# full-bridge-driver.net
KiCad netlist of a schematic drawn in Altium Designer
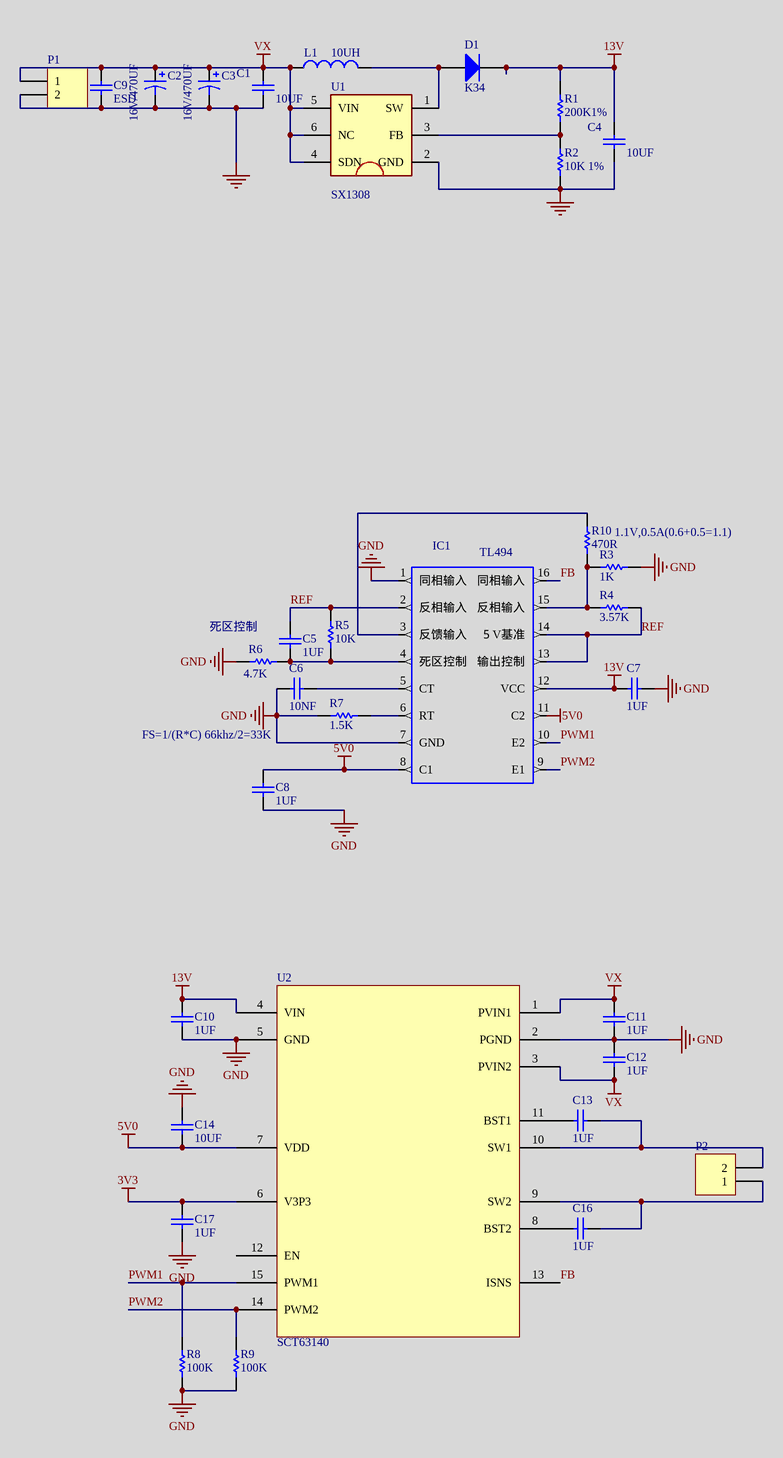
[diagram p0: full-bridge-driver.SchDoc]

(export (version "E")
  (design (tool "Eeschema 10.0.6"))
  (components
    (comp (ref "C1")
      (value "10UF")
      (footprint "C1608-0603N")
      (description "Capacitor")
      (fields
        (field (name "MANUFACTURER") "Generic Components")
        (field (name "PUBLISHER") "Altium Hobart Technology Centre")
      )
      (libsource (lib "Miscellaneous Devices") (part "Cap"))
    )
    (comp (ref "C2")
      (value "16V/470UF")
      (footprint "EC_8mm - 3.5MM")
      (description "Polarized Capacitor (Surface Mount)")
      (fields (field (name "PUBLISHER") "Altium Limited"))
      (libsource (lib "Miscellaneous Devices") (part "Cap Pol3"))
    )
    (comp (ref "C3")
      (value "16V/470UF")
      (footprint "EC_8mm - 3.5MM")
      (description "Polarized Capacitor (Surface Mount)")
      (fields (field (name "PUBLISHER") "Altium Limited"))
      (libsource (lib "Miscellaneous Devices") (part "Cap Pol3"))
    )
    (comp (ref "C4")
      (value "10UF")
      (footprint "C1608-0603N")
      (description "Capacitor")
      (fields
        (field (name "MANUFACTURER") "Generic Components")
        (field (name "PUBLISHER") "Altium Hobart Technology Centre")
      )
      (libsource (lib "Miscellaneous Devices") (part "Cap"))
    )
    (comp (ref "C5")
      (value "1UF")
      (footprint "C1608-0603N")
      (description "Capacitor")
      (fields
        (field (name "MANUFACTURER") "Generic Components")
        (field (name "PUBLISHER") "Altium Hobart Technology Centre")
      )
      (libsource (lib "Miscellaneous Devices") (part "Cap"))
    )
    (comp (ref "C6")
      (value "10NF")
      (footprint "C1608-0603N")
      (description "Capacitor")
      (fields
        (field (name "MANUFACTURER") "Generic Components")
        (field (name "PUBLISHER") "Altium Hobart Technology Centre")
      )
      (libsource (lib "Miscellaneous Devices") (part "Cap"))
    )
    (comp (ref "C7")
      (value "1UF")
      (footprint "C1608-0603N")
      (description "Capacitor")
      (fields
        (field (name "MANUFACTURER") "Generic Components")
        (field (name "PUBLISHER") "Altium Hobart Technology Centre")
      )
      (libsource (lib "Miscellaneous Devices") (part "Cap"))
    )
    (comp (ref "C8")
      (value "1UF")
      (footprint "C1608-0603N")
      (description "Capacitor")
      (fields
        (field (name "MANUFACTURER") "Generic Components")
        (field (name "PUBLISHER") "Altium Hobart Technology Centre")
      )
      (libsource (lib "Miscellaneous Devices") (part "Cap"))
    )
    (comp (ref "C9")
      (value "ESD")
      (footprint "C1608-0603N")
      (description "压敏电阻")
      (libsource (lib "WSK_Lib") (part "Cap"))
    )
    (comp (ref "C10")
      (value "1UF")
      (footprint "C1608-0603N")
      (description "Capacitor")
      (fields
        (field (name "MANUFACTURER") "Generic Components")
        (field (name "PUBLISHER") "Altium Hobart Technology Centre")
      )
      (libsource (lib "Miscellaneous Devices") (part "Cap"))
    )
    (comp (ref "C11")
      (value "1UF")
      (footprint "C1608-0603N")
      (description "Capacitor")
      (fields
        (field (name "MANUFACTURER") "Generic Components")
        (field (name "PUBLISHER") "Altium Hobart Technology Centre")
      )
      (libsource (lib "Miscellaneous Devices") (part "Cap"))
    )
    (comp (ref "C12")
      (value "1UF")
      (footprint "C1608-0603N")
      (description "Capacitor")
      (fields
        (field (name "MANUFACTURER") "Generic Components")
        (field (name "PUBLISHER") "Altium Hobart Technology Centre")
      )
      (libsource (lib "Miscellaneous Devices") (part "Cap"))
    )
    (comp (ref "C13")
      (value "1UF")
      (footprint "C1608-0603N")
      (description "Capacitor")
      (fields
        (field (name "MANUFACTURER") "Generic Components")
        (field (name "PUBLISHER") "Altium Hobart Technology Centre")
      )
      (libsource (lib "Miscellaneous Devices") (part "Cap"))
    )
    (comp (ref "C14")
      (value "10UF")
      (footprint "C1608-0603N")
      (description "Capacitor")
      (fields
        (field (name "MANUFACTURER") "Generic Components")
        (field (name "PUBLISHER") "Altium Hobart Technology Centre")
      )
      (libsource (lib "Miscellaneous Devices") (part "Cap"))
    )
    (comp (ref "C16")
      (value "1UF")
      (footprint "C1608-0603N")
      (description "Capacitor")
      (fields
        (field (name "MANUFACTURER") "Generic Components")
        (field (name "PUBLISHER") "Altium Hobart Technology Centre")
      )
      (libsource (lib "Miscellaneous Devices") (part "Cap"))
    )
    (comp (ref "C17")
      (value "1UF")
      (footprint "C1608-0603N")
      (description "Capacitor")
      (fields
        (field (name "MANUFACTURER") "Generic Components")
        (field (name "PUBLISHER") "Altium Hobart Technology Centre")
      )
      (libsource (lib "Miscellaneous Devices") (part "Cap"))
    )
    (comp (ref "D1")
      (value "K34")
      (footprint "DIODE_1206N")
      (description "Default Diode")
      (fields
        (field (name "MANUFACTURER") "Generic Components")
        (field (name "PUBLISHER") "Altium Hobart Technology Centre")
      )
      (libsource (lib "Miscellaneous Devices") (part "Diode"))
    )
    (comp (ref "IC1") (value "TL494") (footprint "SOP16") (libsource (lib "*") (part "TL494")))
    (comp (ref "L1")
      (value "10UH")
      (footprint "252010")
      (description "Inductor")
      (fields (field (name "PUBLISHER") "Altium Limited"))
      (libsource (lib "Miscellaneous Devices") (part "Inductor"))
    )
    (comp (ref "P1")
      (value "~")
      (footprint "XHB_2pin_2.54mm")
      (description "Header, 2-Pin")
      (fields (field (name "PUBLISHER") "Altium Limited"))
      (libsource (lib "Miscellaneous Connectors") (part "Header 2"))
    )
    (comp (ref "P2")
      (value "~")
      (footprint "XHB_2pin_2.54mm")
      (description "Header, 2-Pin")
      (fields (field (name "PUBLISHER") "Altium Limited"))
      (libsource (lib "") (part "Header 2_1"))
    )
    (comp (ref "R1")
      (value "200K1%")
      (footprint "C1608-0603N")
      (description "Resistor")
      (fields
        (field (name "MANUFACTURER") "Generic Components")
        (field (name "PUBLISHER") "Altium Hobart Technology Centre")
      )
      (libsource (lib "Miscellaneous Devices") (part "Res1"))
    )
    (comp (ref "R2")
      (value "10K 1%")
      (footprint "C1608-0603N")
      (description "Resistor")
      (fields
        (field (name "MANUFACTURER") "Generic Components")
        (field (name "PUBLISHER") "Altium Hobart Technology Centre")
      )
      (libsource (lib "Miscellaneous Devices") (part "Res1"))
    )
    (comp (ref "R3")
      (value "1K")
      (footprint "C1608-0603N")
      (description "Resistor")
      (fields
        (field (name "MANUFACTURER") "Generic Components")
        (field (name "PUBLISHER") "Altium Hobart Technology Centre")
      )
      (libsource (lib "Miscellaneous Devices") (part "Res1"))
    )
    (comp (ref "R4")
      (value "3.57K")
      (footprint "C1608-0603N")
      (description "Resistor")
      (fields
        (field (name "MANUFACTURER") "Generic Components")
        (field (name "PUBLISHER") "Altium Hobart Technology Centre")
      )
      (libsource (lib "Miscellaneous Devices") (part "Res1"))
    )
    (comp (ref "R5")
      (value "10K")
      (footprint "C1608-0603N")
      (description "Resistor")
      (fields
        (field (name "MANUFACTURER") "Generic Components")
        (field (name "PUBLISHER") "Altium Hobart Technology Centre")
      )
      (libsource (lib "Miscellaneous Devices") (part "Res1"))
    )
    (comp (ref "R6")
      (value "4.7K")
      (footprint "C1608-0603N")
      (description "Resistor")
      (fields
        (field (name "MANUFACTURER") "Generic Components")
        (field (name "PUBLISHER") "Altium Hobart Technology Centre")
      )
      (libsource (lib "Miscellaneous Devices") (part "Res1"))
    )
    (comp (ref "R7")
      (value "1.5K")
      (footprint "C1608-0603N")
      (description "Resistor")
      (fields
        (field (name "MANUFACTURER") "Generic Components")
        (field (name "PUBLISHER") "Altium Hobart Technology Centre")
      )
      (libsource (lib "Miscellaneous Devices") (part "Res1"))
    )
    (comp (ref "R8")
      (value "100K")
      (footprint "C1608-0603N")
      (description "Resistor")
      (fields
        (field (name "MANUFACTURER") "Generic Components")
        (field (name "PUBLISHER") "Altium Hobart Technology Centre")
      )
      (libsource (lib "Miscellaneous Devices") (part "Res1"))
    )
    (comp (ref "R9")
      (value "100K")
      (footprint "C1608-0603N")
      (description "Resistor")
      (fields
        (field (name "MANUFACTURER") "Generic Components")
        (field (name "PUBLISHER") "Altium Hobart Technology Centre")
      )
      (libsource (lib "Miscellaneous Devices") (part "Res1"))
    )
    (comp (ref "R10")
      (value "470R")
      (footprint "C1608-0603N")
      (description "Resistor")
      (fields
        (field (name "MANUFACTURER") "Generic Components")
        (field (name "PUBLISHER") "Altium Hobart Technology Centre")
      )
      (libsource (lib "Miscellaneous Devices") (part "Res1"))
    )
    (comp (ref "U1") (value "SX1308") (footprint "SOT23-6") (libsource (lib "Component") (part "SX1308")))
    (comp (ref "U2")
      (value "SCT63140")
      (footprint "FCQFN-15L")
      (libsource (lib "Component") (part "SCT63140"))
    )
  )
  (nets
    (net (code "1") (name "/FB") (class "Default")
      (node (ref "IC1") (pin "16") (pinfunction "同相输入_16") (pintype "output"))
      (node (ref "U2") (pin "13") (pinfunction "ISNS_13") (pintype "passive"))
    )
    (net (code "2") (name "/PWM1") (class "Default")
      (node (ref "IC1") (pin "10") (pinfunction "E2_10") (pintype "output"))
      (node (ref "R8") (pin "1") (pinfunction "1_1") (pintype "passive"))
      (node (ref "U2") (pin "15") (pinfunction "PWM1_15") (pintype "passive"))
    )
    (net (code "3") (name "/PWM2") (class "Default")
      (node (ref "IC1") (pin "9") (pinfunction "E1_9") (pintype "output"))
      (node (ref "R9") (pin "1") (pinfunction "1_1") (pintype "passive"))
      (node (ref "U2") (pin "14") (pinfunction "PWM2_14") (pintype "passive"))
    )
    (net (code "4") (name "/REF") (class "Default")
      (node (ref "C5") (pin "2") (pinfunction "2_2") (pintype "passive"))
      (node (ref "IC1") (pin "13") (pinfunction "输出控制_13") (pintype "output"))
      (node (ref "IC1") (pin "14") (pinfunction "５V基准_14") (pintype "output"))
      (node (ref "IC1") (pin "2") (pinfunction "反相输入_2") (pintype "output"))
      (node (ref "R4") (pin "1") (pinfunction "1_1") (pintype "passive"))
      (node (ref "R5") (pin "2") (pinfunction "2_2") (pintype "passive"))
    )
    (net (code "5") (name "3V3") (class "Default")
      (node (ref "C17") (pin "2") (pinfunction "2_2") (pintype "passive"))
      (node (ref "U2") (pin "6") (pinfunction "V3P3_6") (pintype "passive"))
    )
    (net (code "6") (name "5V0") (class "Default")
      (node (ref "C14") (pin "2") (pinfunction "2_2") (pintype "passive"))
      (node (ref "C8") (pin "2") (pinfunction "2_2") (pintype "passive"))
      (node (ref "IC1") (pin "11") (pinfunction "C2_11") (pintype "output"))
      (node (ref "IC1") (pin "8") (pinfunction "C1_8") (pintype "output"))
      (node (ref "U2") (pin "7") (pinfunction "VDD_7") (pintype "passive"))
    )
    (net (code "7") (name "13V") (class "Default")
      (node (ref "C10") (pin "2") (pinfunction "2_2") (pintype "passive"))
      (node (ref "C4") (pin "1") (pinfunction "1_1") (pintype "passive"))
      (node (ref "C7") (pin "1") (pinfunction "1_1") (pintype "passive"))
      (node (ref "D1") (pin "2") (pinfunction "K_2") (pintype "passive"))
      (node (ref "IC1") (pin "12") (pinfunction "VCC_12") (pintype "output"))
      (node (ref "R1") (pin "1") (pinfunction "1_1") (pintype "passive"))
      (node (ref "U2") (pin "4") (pinfunction "VIN_4") (pintype "passive"))
    )
    (net (code "8") (name "GND") (class "Default")
      (node (ref "C1") (pin "2") (pinfunction "2_2") (pintype "passive"))
      (node (ref "C10") (pin "1") (pinfunction "1_1") (pintype "passive"))
      (node (ref "C11") (pin "1") (pinfunction "1_1") (pintype "passive"))
      (node (ref "C12") (pin "2") (pinfunction "2_2") (pintype "passive"))
      (node (ref "C14") (pin "1") (pinfunction "1_1") (pintype "passive"))
      (node (ref "C17") (pin "1") (pinfunction "1_1") (pintype "passive"))
      (node (ref "C2") (pin "2") (pinfunction "2_2") (pintype "passive"))
      (node (ref "C3") (pin "2") (pinfunction "2_2") (pintype "passive"))
      (node (ref "C4") (pin "2") (pinfunction "2_2") (pintype "passive"))
      (node (ref "C6") (pin "1") (pinfunction "1_1") (pintype "passive"))
      (node (ref "C7") (pin "2") (pinfunction "2_2") (pintype "passive"))
      (node (ref "C8") (pin "1") (pinfunction "1_1") (pintype "passive"))
      (node (ref "C9") (pin "2") (pinfunction "2_2") (pintype "passive"))
      (node (ref "IC1") (pin "1") (pinfunction "同相输入_1") (pintype "output"))
      (node (ref "IC1") (pin "7") (pinfunction "GND_7") (pintype "output"))
      (node (ref "P1") (pin "2") (pinfunction "2_2") (pintype "passive"))
      (node (ref "R2") (pin "2") (pinfunction "2_2") (pintype "passive"))
      (node (ref "R3") (pin "1") (pinfunction "1_1") (pintype "passive"))
      (node (ref "R6") (pin "1") (pinfunction "1_1") (pintype "passive"))
      (node (ref "R7") (pin "1") (pinfunction "1_1") (pintype "passive"))
      (node (ref "R8") (pin "2") (pinfunction "2_2") (pintype "passive"))
      (node (ref "R9") (pin "2") (pinfunction "2_2") (pintype "passive"))
      (node (ref "U1") (pin "2") (pinfunction "GND_2") (pintype "passive"))
      (node (ref "U2") (pin "2") (pinfunction "PGND_2") (pintype "passive"))
      (node (ref "U2") (pin "5") (pinfunction "GND_5") (pintype "passive"))
    )
    (net (code "9") (name "Net-(D1-A)") (class "Default")
      (node (ref "D1") (pin "1") (pinfunction "A_1") (pintype "passive"))
      (node (ref "L1") (pin "2") (pinfunction "2_2") (pintype "passive"))
      (node (ref "U1") (pin "1") (pinfunction "SW_1") (pintype "passive"))
    )
    (net (code "10") (name "Net-(IC1-CT)") (class "Default")
      (node (ref "C6") (pin "2") (pinfunction "2_2") (pintype "passive"))
      (node (ref "IC1") (pin "5") (pinfunction "CT_5") (pintype "output"))
    )
    (net (code "11") (name "Net-(IC1-RT)") (class "Default")
      (node (ref "IC1") (pin "6") (pinfunction "RT_6") (pintype "output"))
      (node (ref "R7") (pin "2") (pinfunction "2_2") (pintype "passive"))
    )
    (net (code "12") (name "Net-(IC1-反相输入-Pad15)") (class "Default")
      (node (ref "IC1") (pin "15") (pinfunction "反相输入_15") (pintype "output"))
      (node (ref "R10") (pin "2") (pinfunction "2_2") (pintype "passive"))
      (node (ref "R3") (pin "2") (pinfunction "2_2") (pintype "passive"))
      (node (ref "R4") (pin "2") (pinfunction "2_2") (pintype "passive"))
    )
    (net (code "13") (name "Net-(IC1-反馈输入)") (class "Default")
      (node (ref "IC1") (pin "3") (pinfunction "反馈输入_3") (pintype "output"))
      (node (ref "R10") (pin "1") (pinfunction "1_1") (pintype "passive"))
    )
    (net (code "14") (name "Net-(IC1-死区控制)") (class "Default")
      (node (ref "C5") (pin "1") (pinfunction "1_1") (pintype "passive"))
      (node (ref "IC1") (pin "4") (pinfunction "死区控制_4") (pintype "output"))
      (node (ref "R5") (pin "1") (pinfunction "1_1") (pintype "passive"))
      (node (ref "R6") (pin "2") (pinfunction "2_2") (pintype "passive"))
    )
    (net (code "15") (name "Net-(U1-FB)") (class "Default")
      (node (ref "R1") (pin "2") (pinfunction "2_2") (pintype "passive"))
      (node (ref "R2") (pin "1") (pinfunction "1_1") (pintype "passive"))
      (node (ref "U1") (pin "3") (pinfunction "FB_3") (pintype "passive"))
    )
    (net (code "16") (name "Net-(U2-BST1)") (class "Default")
      (node (ref "C13") (pin "2") (pinfunction "2_2") (pintype "passive"))
      (node (ref "U2") (pin "11") (pinfunction "BST1_11") (pintype "passive"))
    )
    (net (code "17") (name "Net-(U2-BST2)") (class "Default")
      (node (ref "C16") (pin "2") (pinfunction "2_2") (pintype "passive"))
      (node (ref "U2") (pin "8") (pinfunction "BST2_8") (pintype "passive"))
    )
    (net (code "18") (name "Net-(U2-SW1)") (class "Default")
      (node (ref "C13") (pin "1") (pinfunction "1_1") (pintype "passive"))
      (node (ref "P2") (pin "2") (pinfunction "2_2") (pintype "passive"))
      (node (ref "U2") (pin "10") (pinfunction "SW1_10") (pintype "passive"))
    )
    (net (code "19") (name "Net-(U2-SW2)") (class "Default")
      (node (ref "C16") (pin "1") (pinfunction "1_1") (pintype "passive"))
      (node (ref "P2") (pin "1") (pinfunction "1_1") (pintype "passive"))
      (node (ref "U2") (pin "9") (pinfunction "SW2_9") (pintype "passive"))
    )
    (net (code "20") (name "VX") (class "Default")
      (node (ref "C1") (pin "1") (pinfunction "1_1") (pintype "passive"))
      (node (ref "C11") (pin "2") (pinfunction "2_2") (pintype "passive"))
      (node (ref "C12") (pin "1") (pinfunction "1_1") (pintype "passive"))
      (node (ref "C2") (pin "1") (pinfunction "1_1") (pintype "passive"))
      (node (ref "C3") (pin "1") (pinfunction "1_1") (pintype "passive"))
      (node (ref "C9") (pin "1") (pinfunction "1_1") (pintype "passive"))
      (node (ref "L1") (pin "1") (pinfunction "1_1") (pintype "passive"))
      (node (ref "P1") (pin "1") (pinfunction "1_1") (pintype "passive"))
      (node (ref "U1") (pin "4") (pinfunction "SDN_4") (pintype "passive"))
      (node (ref "U1") (pin "5") (pinfunction "VIN_5") (pintype "passive"))
      (node (ref "U1") (pin "6") (pinfunction "NC_6") (pintype "passive"))
      (node (ref "U2") (pin "1") (pinfunction "PVIN1_1") (pintype "passive"))
      (node (ref "U2") (pin "3") (pinfunction "PVIN2_3") (pintype "passive"))
    )
    (net (code "21") (name "unconnected-(U2-EN-Pad12)") (class "Default")
      (node (ref "U2") (pin "12") (pinfunction "EN_12") (pintype "passive"))
    )
  )
)
